# Saab_ACC_5045158_1.net
KiCad netlist of a schematic drawn in EAGLE
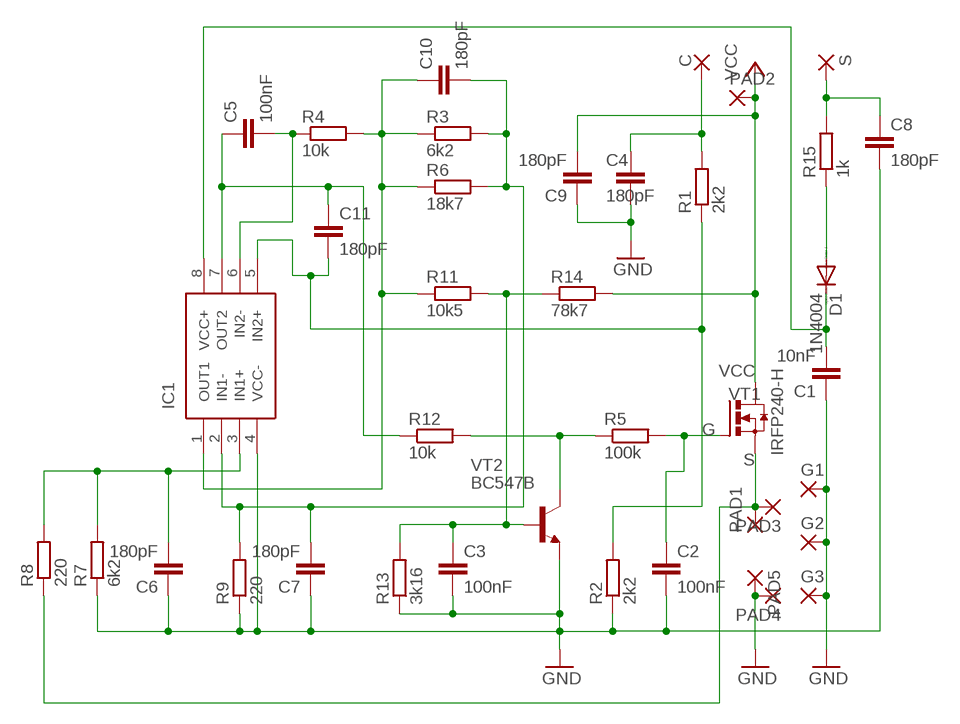
[diagram p0: schematic, sheet 1]

(export (version "E")
  (design (tool "Eeschema 10.0.6"))
  (components
    (comp (ref "C")
      (value "3,17/1,3")
      (footprint "eagle-import:3,17_1,3")
      (libsource (lib "eagle-import") (part "3,17/1,3"))
    )
    (comp (ref "C1")
      (value "10nF")
      (footprint "eagle-import:C2.5-2")
      (libsource (lib "eagle-import") (part "C2.5/2"))
    )
    (comp (ref "C2")
      (value "100nF")
      (footprint "eagle-import:C050-024X044")
      (libsource (lib "eagle-import") (part "C-EU050-024X044"))
    )
    (comp (ref "C3")
      (value "100nF")
      (footprint "eagle-import:C050-024X044")
      (libsource (lib "eagle-import") (part "C-EU050-024X044"))
    )
    (comp (ref "C4")
      (value "180pF")
      (footprint "eagle-import:C0805K")
      (libsource (lib "eagle-import") (part "C-EUC0805K"))
    )
    (comp (ref "C5")
      (value "100nF")
      (footprint "eagle-import:C050-024X044")
      (libsource (lib "eagle-import") (part "C-EU050-024X044"))
    )
    (comp (ref "C6")
      (value "180pF")
      (footprint "eagle-import:C0805K")
      (libsource (lib "eagle-import") (part "C-EUC0805K"))
    )
    (comp (ref "C7")
      (value "180pF")
      (footprint "eagle-import:C0805K")
      (libsource (lib "eagle-import") (part "C-EUC0805K"))
    )
    (comp (ref "C8")
      (value "180pF")
      (footprint "eagle-import:C0805K")
      (libsource (lib "eagle-import") (part "C-EUC0805K"))
    )
    (comp (ref "C9")
      (value "180pF")
      (footprint "eagle-import:C0805K")
      (libsource (lib "eagle-import") (part "C-EUC0805K"))
    )
    (comp (ref "C10")
      (value "180pF")
      (footprint "eagle-import:C0805K")
      (libsource (lib "eagle-import") (part "C-EUC0805K"))
    )
    (comp (ref "C11")
      (value "180pF")
      (footprint "eagle-import:C0805K")
      (libsource (lib "eagle-import") (part "C-EUC0805K"))
    )
    (comp (ref "D1")
      (value "1N4004")
      (footprint "eagle-import:DO41-10")
      (libsource (lib "eagle-import") (part "1N4004"))
    )
    (comp (ref "G1")
      (value "3,81/1,4")
      (footprint "eagle-import:3,81_1,4")
      (libsource (lib "eagle-import") (part "3,81/1,4"))
    )
    (comp (ref "G2")
      (value "3,17/1,3")
      (footprint "eagle-import:3,17_1,3")
      (libsource (lib "eagle-import") (part "3,17/1,3"))
    )
    (comp (ref "G3")
      (value "3,17/1,3")
      (footprint "eagle-import:3,17_1,3")
      (libsource (lib "eagle-import") (part "3,17/1,3"))
    )
    (comp (ref "IC1")
      (value "LM2904YDT")
      (footprint "eagle-import:SOIC127P600X175-8N")
      (fields (field (name "MOUSER_PART_NUMBER") "511-LM2904YDT"))
      (libsource (lib "eagle-import") (part "LM2904YDT"))
    )
    (comp (ref "PAD1")
      (value "SMD5")
      (footprint "eagle-import:SMD2,54-5,08")
      (libsource (lib "eagle-import") (part "SMD5"))
    )
    (comp (ref "PAD2")
      (value "3,81/1,4")
      (footprint "eagle-import:3,81_1,4")
      (libsource (lib "eagle-import") (part "3,81/1,4"))
    )
    (comp (ref "PAD3")
      (value "SMD5")
      (footprint "eagle-import:SMD2,54-5,08")
      (libsource (lib "eagle-import") (part "SMD5"))
    )
    (comp (ref "PAD4")
      (value "SMD5")
      (footprint "eagle-import:SMD2,54-5,08")
      (libsource (lib "eagle-import") (part "SMD5"))
    )
    (comp (ref "PAD5")
      (value "SMD5")
      (footprint "eagle-import:SMD2,54-5,08")
      (libsource (lib "eagle-import") (part "SMD5"))
    )
    (comp (ref "R1")
      (value "2k2")
      (footprint "eagle-import:0204_5")
      (libsource (lib "eagle-import") (part "R-EU_0204/5"))
    )
    (comp (ref "R2")
      (value "2k2")
      (footprint "eagle-import:0204_5")
      (libsource (lib "eagle-import") (part "R-EU_0204/5"))
    )
    (comp (ref "R3")
      (value "6k2")
      (footprint "eagle-import:0204_5")
      (libsource (lib "eagle-import") (part "R-EU_0204/5"))
    )
    (comp (ref "R4")
      (value "10k")
      (footprint "eagle-import:0204_5")
      (libsource (lib "eagle-import") (part "R-EU_0204/5"))
    )
    (comp (ref "R5")
      (value "100k")
      (footprint "eagle-import:0204_5")
      (libsource (lib "eagle-import") (part "R-EU_0204/5"))
    )
    (comp (ref "R6")
      (value "18k7")
      (footprint "eagle-import:0207_10")
      (libsource (lib "eagle-import") (part "resistor_R-EU_0207/10"))
    )
    (comp (ref "R7")
      (value "6k2")
      (footprint "eagle-import:0204_5")
      (libsource (lib "eagle-import") (part "R-EU_0204/5"))
    )
    (comp (ref "R8")
      (value "220")
      (footprint "eagle-import:0204_5")
      (libsource (lib "eagle-import") (part "R-EU_0204/5"))
    )
    (comp (ref "R9")
      (value "220")
      (footprint "eagle-import:0204_5")
      (libsource (lib "eagle-import") (part "R-EU_0204/5"))
    )
    (comp (ref "R11")
      (value "10k5")
      (footprint "eagle-import:0204_7")
      (libsource (lib "eagle-import") (part "R-EU_0204/7"))
    )
    (comp (ref "R12")
      (value "10k")
      (footprint "eagle-import:0204_5")
      (libsource (lib "eagle-import") (part "resistor_R-EU_0204/5"))
    )
    (comp (ref "R13")
      (value "3k16")
      (footprint "eagle-import:0204_7")
      (libsource (lib "eagle-import") (part "R-EU_0204/7"))
    )
    (comp (ref "R14")
      (value "78k7")
      (footprint "eagle-import:0204_7")
      (libsource (lib "eagle-import") (part "R-EU_0204/7"))
    )
    (comp (ref "R15")
      (value "1k")
      (footprint "eagle-import:0204_5")
      (libsource (lib "eagle-import") (part "resistor_R-EU_0204/5"))
    )
    (comp (ref "S")
      (value "3,17/1,3")
      (footprint "eagle-import:3,17_1,3")
      (libsource (lib "eagle-import") (part "3,17/1,3"))
    )
    (comp (ref "VT1")
      (value "IRFP240-H")
      (footprint "eagle-import:TO247BH")
      (libsource (lib "eagle-import") (part "IRFP240-H"))
    )
    (comp (ref "VT2")
      (value "BC547B")
      (footprint "eagle-import:TO92")
      (libsource (lib "eagle-import") (part "BC547B"))
    )
  )
  (nets
    (net (code "1") (name "/G") (class "Default")
      (node (ref "C2") (pin "1") (pinfunction "1_1") (pintype "passive"))
      (node (ref "R5") (pin "2") (pinfunction "2_2") (pintype "passive"))
      (node (ref "VT1") (pin "G") (pinfunction "G_G") (pintype "passive"))
    )
    (net (code "2") (name "/S") (class "Default")
      (node (ref "PAD1") (pin "1") (pinfunction "P_1") (pintype "passive"))
      (node (ref "PAD3") (pin "1") (pinfunction "P_1") (pintype "passive"))
      (node (ref "R8") (pin "1") (pinfunction "1_1") (pintype "passive"))
      (node (ref "VT1") (pin "S") (pinfunction "S_S") (pintype "passive"))
    )
    (net (code "3") (name "GND") (class "Default")
      (node (ref "C1") (pin "1") (pinfunction "1_1") (pintype "passive"))
      (node (ref "C2") (pin "2") (pinfunction "2_2") (pintype "passive"))
      (node (ref "C3") (pin "2") (pinfunction "2_2") (pintype "passive"))
      (node (ref "C4") (pin "2") (pinfunction "2_2") (pintype "passive"))
      (node (ref "C6") (pin "1") (pinfunction "1_1") (pintype "passive"))
      (node (ref "C7") (pin "1") (pinfunction "1_1") (pintype "passive"))
      (node (ref "C8") (pin "2") (pinfunction "2_2") (pintype "passive"))
      (node (ref "C9") (pin "1") (pinfunction "1_1") (pintype "passive"))
      (node (ref "G1") (pin "1") (pinfunction "P_1") (pintype "passive"))
      (node (ref "G2") (pin "1") (pinfunction "P_1") (pintype "passive"))
      (node (ref "G3") (pin "1") (pinfunction "P_1") (pintype "passive"))
      (node (ref "IC1") (pin "4") (pinfunction "VCC-_4") (pintype "bidirectional"))
      (node (ref "PAD4") (pin "1") (pinfunction "P_1") (pintype "passive"))
      (node (ref "PAD5") (pin "1") (pinfunction "P_1") (pintype "passive"))
      (node (ref "R13") (pin "1") (pinfunction "1_1") (pintype "passive"))
      (node (ref "R2") (pin "1") (pinfunction "1_1") (pintype "passive"))
      (node (ref "R7") (pin "1") (pinfunction "1_1") (pintype "passive"))
      (node (ref "R9") (pin "1") (pinfunction "1_1") (pintype "passive"))
      (node (ref "VT2") (pin "1") (pinfunction "E_1") (pintype "passive"))
    )
    (net (code "4") (name "Net-(C-P)") (class "Default")
      (node (ref "C") (pin "1") (pinfunction "P_1") (pintype "passive"))
      (node (ref "C4") (pin "1") (pinfunction "1_1") (pintype "passive"))
      (node (ref "R1") (pin "2") (pinfunction "2_2") (pintype "passive"))
    )
    (net (code "5") (name "Net-(D1-PadA)") (class "Default")
      (node (ref "D1") (pin "A") (pinfunction "A_A") (pintype "passive"))
      (node (ref "R15") (pin "1") (pinfunction "1_1") (pintype "passive"))
    )
    (net (code "6") (name "Net-(IC1-IN1+)") (class "Default")
      (node (ref "C6") (pin "2") (pinfunction "2_2") (pintype "passive"))
      (node (ref "IC1") (pin "3") (pinfunction "IN1+_3") (pintype "bidirectional"))
      (node (ref "R7") (pin "2") (pinfunction "2_2") (pintype "passive"))
      (node (ref "R8") (pin "2") (pinfunction "2_2") (pintype "passive"))
    )
    (net (code "7") (name "Net-(IC1-IN1-)") (class "Default")
      (node (ref "C10") (pin "2") (pinfunction "2_2") (pintype "passive"))
      (node (ref "C7") (pin "2") (pinfunction "2_2") (pintype "passive"))
      (node (ref "IC1") (pin "2") (pinfunction "IN1-_2") (pintype "bidirectional"))
      (node (ref "R3") (pin "2") (pinfunction "2_2") (pintype "passive"))
      (node (ref "R6") (pin "2") (pinfunction "2_2") (pintype "passive"))
      (node (ref "R9") (pin "2") (pinfunction "2_2") (pintype "passive"))
    )
    (net (code "8") (name "Net-(IC1-IN2+)") (class "Default")
      (node (ref "C11") (pin "2") (pinfunction "2_2") (pintype "passive"))
      (node (ref "IC1") (pin "5") (pinfunction "IN2+_5") (pintype "bidirectional"))
      (node (ref "R1") (pin "1") (pinfunction "1_1") (pintype "passive"))
      (node (ref "R2") (pin "2") (pinfunction "2_2") (pintype "passive"))
    )
    (net (code "9") (name "Net-(IC1-IN2-)") (class "Default")
      (node (ref "C5") (pin "2") (pinfunction "2_2") (pintype "passive"))
      (node (ref "IC1") (pin "6") (pinfunction "IN2-_6") (pintype "bidirectional"))
      (node (ref "R4") (pin "1") (pinfunction "1_1") (pintype "passive"))
    )
    (net (code "10") (name "Net-(IC1-OUT1)") (class "Default")
      (node (ref "C10") (pin "1") (pinfunction "1_1") (pintype "passive"))
      (node (ref "IC1") (pin "1") (pinfunction "OUT1_1") (pintype "bidirectional"))
      (node (ref "R11") (pin "1") (pinfunction "1_1") (pintype "passive"))
      (node (ref "R3") (pin "1") (pinfunction "1_1") (pintype "passive"))
      (node (ref "R4") (pin "2") (pinfunction "2_2") (pintype "passive"))
      (node (ref "R6") (pin "1") (pinfunction "1_1") (pintype "passive"))
    )
    (net (code "11") (name "Net-(IC1-OUT2)") (class "Default")
      (node (ref "C11") (pin "1") (pinfunction "1_1") (pintype "passive"))
      (node (ref "C5") (pin "1") (pinfunction "1_1") (pintype "passive"))
      (node (ref "IC1") (pin "7") (pinfunction "OUT2_7") (pintype "bidirectional"))
      (node (ref "R12") (pin "1") (pinfunction "1_1") (pintype "passive"))
    )
    (net (code "12") (name "Net-(IC1-VCC+)") (class "Default")
      (node (ref "C1") (pin "2") (pinfunction "2_2") (pintype "passive"))
      (node (ref "D1") (pin "C") (pinfunction "C_C") (pintype "passive"))
      (node (ref "IC1") (pin "8") (pinfunction "VCC+_8") (pintype "bidirectional"))
    )
    (net (code "13") (name "Net-(S-P)") (class "Default")
      (node (ref "C8") (pin "1") (pinfunction "1_1") (pintype "passive"))
      (node (ref "R15") (pin "2") (pinfunction "2_2") (pintype "passive"))
      (node (ref "S") (pin "1") (pinfunction "P_1") (pintype "passive"))
    )
    (net (code "14") (name "Net-(VT2-B)") (class "Default")
      (node (ref "C3") (pin "1") (pinfunction "1_1") (pintype "passive"))
      (node (ref "R11") (pin "2") (pinfunction "2_2") (pintype "passive"))
      (node (ref "R13") (pin "2") (pinfunction "2_2") (pintype "passive"))
      (node (ref "R14") (pin "1") (pinfunction "1_1") (pintype "passive"))
      (node (ref "VT2") (pin "2") (pinfunction "B_2") (pintype "passive"))
    )
    (net (code "15") (name "Net-(VT2-C)") (class "Default")
      (node (ref "R12") (pin "2") (pinfunction "2_2") (pintype "passive"))
      (node (ref "R5") (pin "1") (pinfunction "1_1") (pintype "passive"))
      (node (ref "VT2") (pin "3") (pinfunction "C_3") (pintype "passive"))
    )
    (net (code "16") (name "VCC") (class "Default")
      (node (ref "C9") (pin "2") (pinfunction "2_2") (pintype "passive"))
      (node (ref "PAD2") (pin "1") (pinfunction "P_1") (pintype "passive"))
      (node (ref "R14") (pin "2") (pinfunction "2_2") (pintype "passive"))
      (node (ref "VT1") (pin "D") (pinfunction "D_D") (pintype "passive"))
    )
  )
)
